# LCC_Resonant_Charging_Board.net
KiCad netlist of a schematic drawn in Altium Designer
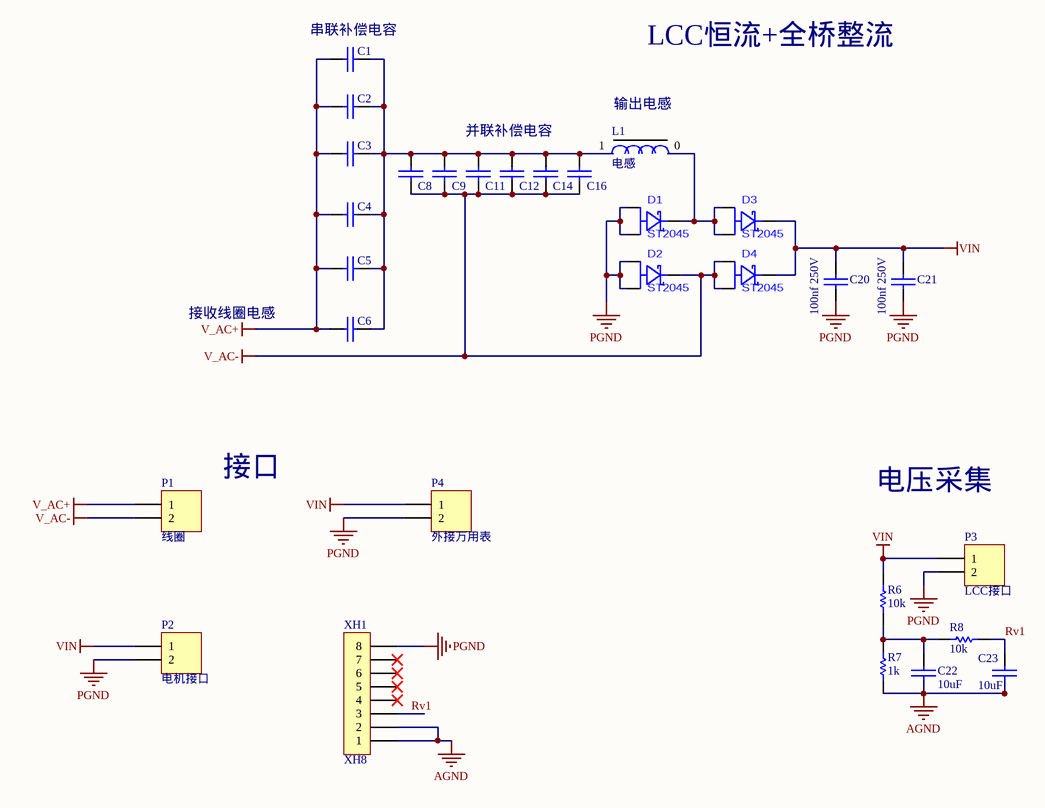
[diagram p0: LCC Resonant Charging Board.SchDoc]

(export (version "E")
  (design (tool "Eeschema 10.0.6"))
  (components
    (comp (ref "C1")
      (value "~")
      (footprint "1206C")
      (description "无极性电容")
      (libsource (lib "电容") (part "CAP"))
    )
    (comp (ref "C2")
      (value "~")
      (footprint "1206C")
      (description "无极性电容")
      (libsource (lib "电容") (part "CAP"))
    )
    (comp (ref "C3")
      (value "~")
      (footprint "1206C")
      (description "无极性电容")
      (libsource (lib "电容") (part "CAP"))
    )
    (comp (ref "C4")
      (value "~")
      (footprint "1206C")
      (description "无极性电容")
      (libsource (lib "电容") (part "CAP"))
    )
    (comp (ref "C5")
      (value "~")
      (footprint "1206C")
      (description "无极性电容")
      (libsource (lib "电容") (part "CAP"))
    )
    (comp (ref "C6")
      (value "~")
      (footprint "1206C")
      (description "无极性电容")
      (libsource (lib "电容") (part "CAP"))
    )
    (comp (ref "C8")
      (value "~")
      (footprint "1206C")
      (description "无极性电容")
      (libsource (lib "电容") (part "CAP"))
    )
    (comp (ref "C9")
      (value "~")
      (footprint "1206C")
      (description "无极性电容")
      (libsource (lib "电容") (part "CAP"))
    )
    (comp (ref "C11")
      (value "~")
      (footprint "1206C")
      (description "无极性电容")
      (libsource (lib "电容") (part "CAP"))
    )
    (comp (ref "C12")
      (value "~")
      (footprint "1206C")
      (description "无极性电容")
      (libsource (lib "电容") (part "CAP"))
    )
    (comp (ref "C14")
      (value "~")
      (footprint "1206C")
      (description "无极性电容")
      (libsource (lib "电容") (part "CAP"))
    )
    (comp (ref "C16")
      (value "~")
      (footprint "1206C")
      (description "无极性电容")
      (libsource (lib "电容") (part "CAP"))
    )
    (comp (ref "C20")
      (value "100nf 250V")
      (footprint "1206C")
      (description "无极性电容")
      (libsource (lib "电容") (part "CAP"))
    )
    (comp (ref "C21")
      (value "100nf 250V")
      (footprint "1206C")
      (description "无极性电容")
      (libsource (lib "电容") (part "CAP"))
    )
    (comp (ref "C22")
      (value "10uF")
      (footprint "0603C")
      (description "无极性电容")
      (libsource (lib "电容") (part "CAP"))
    )
    (comp (ref "C23")
      (value "10uF")
      (footprint "0603C")
      (description "无极性电容")
      (libsource (lib "电容") (part "CAP"))
    )
    (comp (ref "D1") (value "ST2045") (footprint "FM10U100") (libsource (lib "ST2045 20A") (part "ST2045")))
    (comp (ref "D2") (value "ST2045") (footprint "FM10U100") (libsource (lib "ST2045 20A") (part "ST2045")))
    (comp (ref "D3") (value "ST2045") (footprint "FM10U100") (libsource (lib "ST2045 20A") (part "ST2045")))
    (comp (ref "D4") (value "ST2045") (footprint "FM10U100") (libsource (lib "ST2045 20A") (part "ST2045")))
    (comp (ref "L1") (value "电感") (footprint "lcc电感") (libsource (lib "电感") (part "电感")))
    (comp (ref "P1")
      (value "线圈")
      (footprint "线圈接口")
      (description "Header, 2-Pin")
      (fields (field (name "PUBLISHER") "Altium Limited"))
      (libsource (lib "Miscellaneous Connectors") (part "Header 2"))
    )
    (comp (ref "P2")
      (value "电机接口")
      (footprint "XT30U-M")
      (description "Header, 2-Pin")
      (fields (field (name "PUBLISHER") "Altium Limited"))
      (libsource (lib "Miscellaneous Connectors") (part "Header 2"))
    )
    (comp (ref "P3")
      (value "LCC接口")
      (footprint "XT30U-M")
      (description "Header, 2-Pin")
      (fields (field (name "PUBLISHER") "Altium Limited"))
      (libsource (lib "Miscellaneous Connectors") (part "Header 2"))
    )
    (comp (ref "P4")
      (value "外接万用表")
      (footprint "HDR1X2")
      (description "Header, 2-Pin")
      (fields (field (name "PUBLISHER") "Altium Limited"))
      (libsource (lib "Miscellaneous Connectors") (part "Header 2"))
    )
    (comp (ref "R6") (value "10k") (footprint "0402R") (libsource (lib "电阻") (part "RES")))
    (comp (ref "R7") (value "1k") (footprint "0402R") (libsource (lib "电阻") (part "RES")))
    (comp (ref "R8") (value "10k") (footprint "0402R") (libsource (lib "电阻") (part "RES")))
    (comp (ref "XH1") (value "XH8") (footprint "XH8/2.54mm/180") (libsource (lib "XH，VH") (part "XH8")))
  )
  (nets
    (net (code "1") (name "/Rv1") (class "Default")
      (node (ref "C23") (pin "2") (pinfunction "2_2") (pintype "passive"))
      (node (ref "R8") (pin "1") (pinfunction "1_1") (pintype "passive"))
      (node (ref "XH1") (pin "3") (pinfunction "3_3") (pintype "passive"))
    )
    (net (code "2") (name "AGND") (class "Default")
      (node (ref "C22") (pin "1") (pinfunction "1_1") (pintype "passive"))
      (node (ref "C23") (pin "1") (pinfunction "1_1") (pintype "passive"))
      (node (ref "R7") (pin "1") (pinfunction "1_1") (pintype "passive"))
      (node (ref "XH1") (pin "1") (pinfunction "1_1") (pintype "passive"))
      (node (ref "XH1") (pin "2") (pinfunction "2_2") (pintype "passive"))
    )
    (net (code "3") (name "Net-(C1-Pad2)") (class "Default")
      (node (ref "C1") (pin "2") (pinfunction "2_2") (pintype "passive"))
      (node (ref "C11") (pin "1") (pinfunction "1_1") (pintype "passive"))
      (node (ref "C12") (pin "2") (pinfunction "2_2") (pintype "passive"))
      (node (ref "C14") (pin "2") (pinfunction "2_2") (pintype "passive"))
      (node (ref "C16") (pin "2") (pinfunction "2_2") (pintype "passive"))
      (node (ref "C2") (pin "2") (pinfunction "2_2") (pintype "passive"))
      (node (ref "C3") (pin "2") (pinfunction "2_2") (pintype "passive"))
      (node (ref "C4") (pin "2") (pinfunction "2_2") (pintype "passive"))
      (node (ref "C5") (pin "2") (pinfunction "2_2") (pintype "passive"))
      (node (ref "C6") (pin "1") (pinfunction "1_1") (pintype "passive"))
      (node (ref "C8") (pin "2") (pinfunction "2_2") (pintype "passive"))
      (node (ref "C9") (pin "2") (pinfunction "2_2") (pintype "passive"))
      (node (ref "L1") (pin "1") (pinfunction "1_1") (pintype "passive"))
    )
    (net (code "4") (name "Net-(C22-Pad2)") (class "Default")
      (node (ref "C22") (pin "2") (pinfunction "2_2") (pintype "passive"))
      (node (ref "R6") (pin "1") (pinfunction "1_1") (pintype "passive"))
      (node (ref "R7") (pin "2") (pinfunction "2_2") (pintype "passive"))
      (node (ref "R8") (pin "2") (pinfunction "2_2") (pintype "passive"))
    )
    (net (code "5") (name "Net-(D1-K)") (class "Default")
      (node (ref "D1") (pin "2") (pinfunction "K_2") (pintype "passive"))
      (node (ref "D3") (pin "1") (pinfunction "A_1") (pintype "passive"))
      (node (ref "D3") (pin "3") (pinfunction "A_3") (pintype "passive"))
      (node (ref "L1") (pin "0") (pinfunction "0_0") (pintype "passive"))
    )
    (net (code "6") (name "PGND") (class "Default")
      (node (ref "C20") (pin "1") (pinfunction "1_1") (pintype "passive"))
      (node (ref "C21") (pin "1") (pinfunction "1_1") (pintype "passive"))
      (node (ref "D1") (pin "1") (pinfunction "A_1") (pintype "passive"))
      (node (ref "D1") (pin "3") (pinfunction "A_3") (pintype "passive"))
      (node (ref "D2") (pin "1") (pinfunction "A_1") (pintype "passive"))
      (node (ref "D2") (pin "3") (pinfunction "A_3") (pintype "passive"))
      (node (ref "P2") (pin "2") (pinfunction "2_2") (pintype "passive"))
      (node (ref "P3") (pin "2") (pinfunction "2_2") (pintype "passive"))
      (node (ref "P4") (pin "2") (pinfunction "2_2") (pintype "passive"))
      (node (ref "XH1") (pin "8") (pinfunction "8_8") (pintype "passive"))
    )
    (net (code "7") (name "VIN") (class "Default")
      (node (ref "C20") (pin "2") (pinfunction "2_2") (pintype "passive"))
      (node (ref "C21") (pin "2") (pinfunction "2_2") (pintype "passive"))
      (node (ref "D3") (pin "2") (pinfunction "K_2") (pintype "passive"))
      (node (ref "D4") (pin "2") (pinfunction "K_2") (pintype "passive"))
      (node (ref "P2") (pin "1") (pinfunction "1_1") (pintype "passive"))
      (node (ref "P3") (pin "1") (pinfunction "1_1") (pintype "passive"))
      (node (ref "P4") (pin "1") (pinfunction "1_1") (pintype "passive"))
      (node (ref "R6") (pin "2") (pinfunction "2_2") (pintype "passive"))
    )
    (net (code "8") (name "V_AC+") (class "Default")
      (node (ref "C1") (pin "1") (pinfunction "1_1") (pintype "passive"))
      (node (ref "C2") (pin "1") (pinfunction "1_1") (pintype "passive"))
      (node (ref "C3") (pin "1") (pinfunction "1_1") (pintype "passive"))
      (node (ref "C4") (pin "1") (pinfunction "1_1") (pintype "passive"))
      (node (ref "C5") (pin "1") (pinfunction "1_1") (pintype "passive"))
      (node (ref "C6") (pin "2") (pinfunction "2_2") (pintype "passive"))
      (node (ref "P1") (pin "1") (pinfunction "1_1") (pintype "passive"))
    )
    (net (code "9") (name "V_AC-") (class "Default")
      (node (ref "C11") (pin "2") (pinfunction "2_2") (pintype "passive"))
      (node (ref "C12") (pin "1") (pinfunction "1_1") (pintype "passive"))
      (node (ref "C14") (pin "1") (pinfunction "1_1") (pintype "passive"))
      (node (ref "C16") (pin "1") (pinfunction "1_1") (pintype "passive"))
      (node (ref "C8") (pin "1") (pinfunction "1_1") (pintype "passive"))
      (node (ref "C9") (pin "1") (pinfunction "1_1") (pintype "passive"))
      (node (ref "D2") (pin "2") (pinfunction "K_2") (pintype "passive"))
      (node (ref "D4") (pin "1") (pinfunction "A_1") (pintype "passive"))
      (node (ref "D4") (pin "3") (pinfunction "A_3") (pintype "passive"))
      (node (ref "P1") (pin "2") (pinfunction "2_2") (pintype "passive"))
    )
    (net (code "10") (name "unconnected-(XH1-Pad4)") (class "Default")
      (node (ref "XH1") (pin "4") (pinfunction "4_4") (pintype "passive+no_connect"))
    )
    (net (code "11") (name "unconnected-(XH1-Pad5)") (class "Default")
      (node (ref "XH1") (pin "5") (pinfunction "5_5") (pintype "passive+no_connect"))
    )
    (net (code "12") (name "unconnected-(XH1-Pad6)") (class "Default")
      (node (ref "XH1") (pin "6") (pinfunction "6_6") (pintype "passive+no_connect"))
    )
    (net (code "13") (name "unconnected-(XH1-Pad7)") (class "Default")
      (node (ref "XH1") (pin "7") (pinfunction "7_7") (pintype "passive+no_connect"))
    )
  )
)
